# IMU-ICM-4267-P.net
KiCad netlist of a schematic drawn in Altium Designer
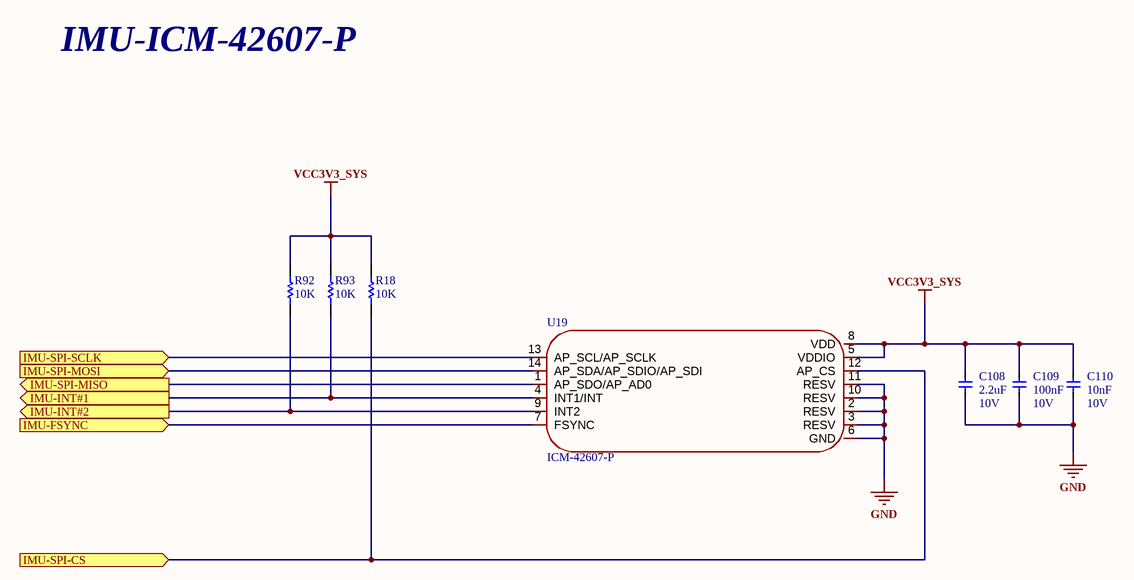
[diagram p0: IMU-ICM-4267-P .SchDoc]

(export (version "E")
  (design (tool "Eeschema 10.0.6"))
  (components
    (comp (ref "C108")
      (value "2.2uF")
      (footprint "CAP-0603")
      (fields (field (name "VOLTAGERATE") "10V"))
      (libsource (lib "DesignLibrary") (part "Capacitor-1"))
    )
    (comp (ref "C109")
      (value "100nF")
      (footprint "CAP-0402")
      (fields (field (name "VOLTAGERATE") "10V"))
      (libsource (lib "DesignLibrary") (part "Capacitor-1"))
    )
    (comp (ref "C110")
      (value "10nF")
      (footprint "CAP-0402")
      (fields (field (name "VOLTAGERATE") "10V"))
      (libsource (lib "DesignLibrary") (part "Capacitor-1"))
    )
    (comp (ref "R18")
      (value "10K")
      (footprint "RES-0402")
      (libsource (lib "DesignLibrary") (part "Resistor-1"))
    )
    (comp (ref "R92")
      (value "10K")
      (footprint "RES-0402")
      (libsource (lib "DesignLibrary") (part "Resistor-1"))
    )
    (comp (ref "R93")
      (value "10K")
      (footprint "RES-0402")
      (libsource (lib "DesignLibrary") (part "Resistor-1"))
    )
    (comp (ref "U19")
      (value "ICM-42607-P")
      (footprint "LGA-14_L3.0-W2.5-P0.50-TL_QMI8658A")
      (libsource (lib "DesignLibrary") (part "ICM-42607-P"))
    )
  )
  (nets
    (net (code "1") (name "/IMU-FSYNC") (class "Default")
      (node (ref "U19") (pin "7") (pinfunction "FSYNC_7") (pintype "passive"))
    )
    (net (code "2") (name "/IMU-INT#1") (class "Default")
      (node (ref "R93") (pin "2") (pintype "passive"))
      (node (ref "U19") (pin "4") (pinfunction "INT1/INT_4") (pintype "passive"))
    )
    (net (code "3") (name "/IMU-INT#2") (class "Default")
      (node (ref "R92") (pin "2") (pintype "passive"))
      (node (ref "U19") (pin "9") (pinfunction "INT2_9") (pintype "passive"))
    )
    (net (code "4") (name "/IMU-SPI-CS") (class "Default")
      (node (ref "R18") (pin "2") (pintype "passive"))
      (node (ref "U19") (pin "12") (pinfunction "AP_CS_12") (pintype "passive"))
    )
    (net (code "5") (name "/IMU-SPI-MISO") (class "Default")
      (node (ref "U19") (pin "1") (pinfunction "AP_SDO/AP_AD0_1") (pintype "passive"))
    )
    (net (code "6") (name "/IMU-SPI-MOSI") (class "Default")
      (node (ref "U19") (pin "14") (pinfunction "AP_SDA/AP_SDIO/AP_SDI_14") (pintype "passive"))
    )
    (net (code "7") (name "/IMU-SPI-SCLK") (class "Default")
      (node (ref "U19") (pin "13") (pinfunction "AP_SCL/AP_SCLK_13") (pintype "passive"))
    )
    (net (code "8") (name "GND") (class "Default")
      (node (ref "C108") (pin "1") (pinfunction "1_1") (pintype "passive"))
      (node (ref "C109") (pin "1") (pinfunction "1_1") (pintype "passive"))
      (node (ref "C110") (pin "1") (pinfunction "1_1") (pintype "passive"))
      (node (ref "U19") (pin "10") (pinfunction "RESV_10") (pintype "passive"))
      (node (ref "U19") (pin "11") (pinfunction "RESV_11") (pintype "passive"))
      (node (ref "U19") (pin "2") (pinfunction "RESV_2") (pintype "passive"))
      (node (ref "U19") (pin "3") (pinfunction "RESV_3") (pintype "passive"))
      (node (ref "U19") (pin "6") (pinfunction "GND_6") (pintype "passive"))
    )
    (net (code "9") (name "VCC3V3_SYS") (class "Default")
      (node (ref "C108") (pin "2") (pinfunction "2_2") (pintype "passive"))
      (node (ref "C109") (pin "2") (pinfunction "2_2") (pintype "passive"))
      (node (ref "C110") (pin "2") (pinfunction "2_2") (pintype "passive"))
      (node (ref "R18") (pin "1") (pintype "passive"))
      (node (ref "R92") (pin "1") (pintype "passive"))
      (node (ref "R93") (pin "1") (pintype "passive"))
      (node (ref "U19") (pin "5") (pinfunction "VDDIO_5") (pintype "passive"))
      (node (ref "U19") (pin "8") (pinfunction "VDD_8") (pintype "passive"))
    )
  )
)
